# environmental_sensor.net
KiCad netlist of a schematic drawn in Altium Designer
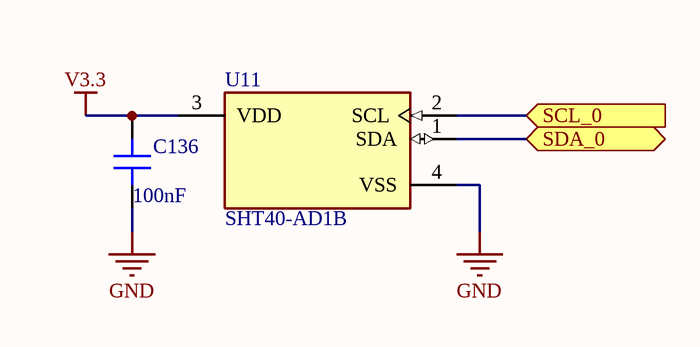
[diagram p0: environmental_sensor.SchDoc]

(export (version "E")
  (design (tool "Eeschema 10.0.6"))
  (components
    (comp (ref "C136")
      (value "100nF")
      (footprint "CAP 0603_1608")
      (description "SMT Capacitor")
      (fields (field (name "MF") "TDK") (field (name "MP") "CGA3E2X7R1E104K080AA"))
      (libsource (lib "Capacitor") (part "Capacitor"))
    )
    (comp (ref "U11")
      (value "SHT40-AD1B")
      (footprint "Sensirion_3_MFG")
      (description "Board Mount Humidity Sensors Humidity and Temperature Sensor")
      (fields (field (name "MF") "Sensirion") (field (name "MP") "SHT40-AD1B-R3"))
      (libsource (lib "EnvSensor") (part "SHT40-AD1B"))
    )
  )
  (nets
    (net (code "1") (name "/SCL_0") (class "Default")
      (node (ref "U11") (pin "2") (pinfunction "SCL_2") (pintype "input"))
    )
    (net (code "2") (name "/SDA_0") (class "Default")
      (node (ref "U11") (pin "1") (pinfunction "SDA_1") (pintype "bidirectional"))
    )
    (net (code "3") (name "GND") (class "Default")
      (node (ref "C136") (pin "2") (pinfunction "2_2") (pintype "passive"))
      (node (ref "U11") (pin "4") (pinfunction "VSS_4") (pintype "power_in"))
    )
    (net (code "4") (name "V3.3") (class "Default")
      (node (ref "C136") (pin "1") (pinfunction "1_1") (pintype "passive"))
      (node (ref "U11") (pin "3") (pinfunction "VDD_3") (pintype "power_in"))
    )
  )
)
